# Power_stage.net
KiCad netlist of a schematic drawn in Altium Designer
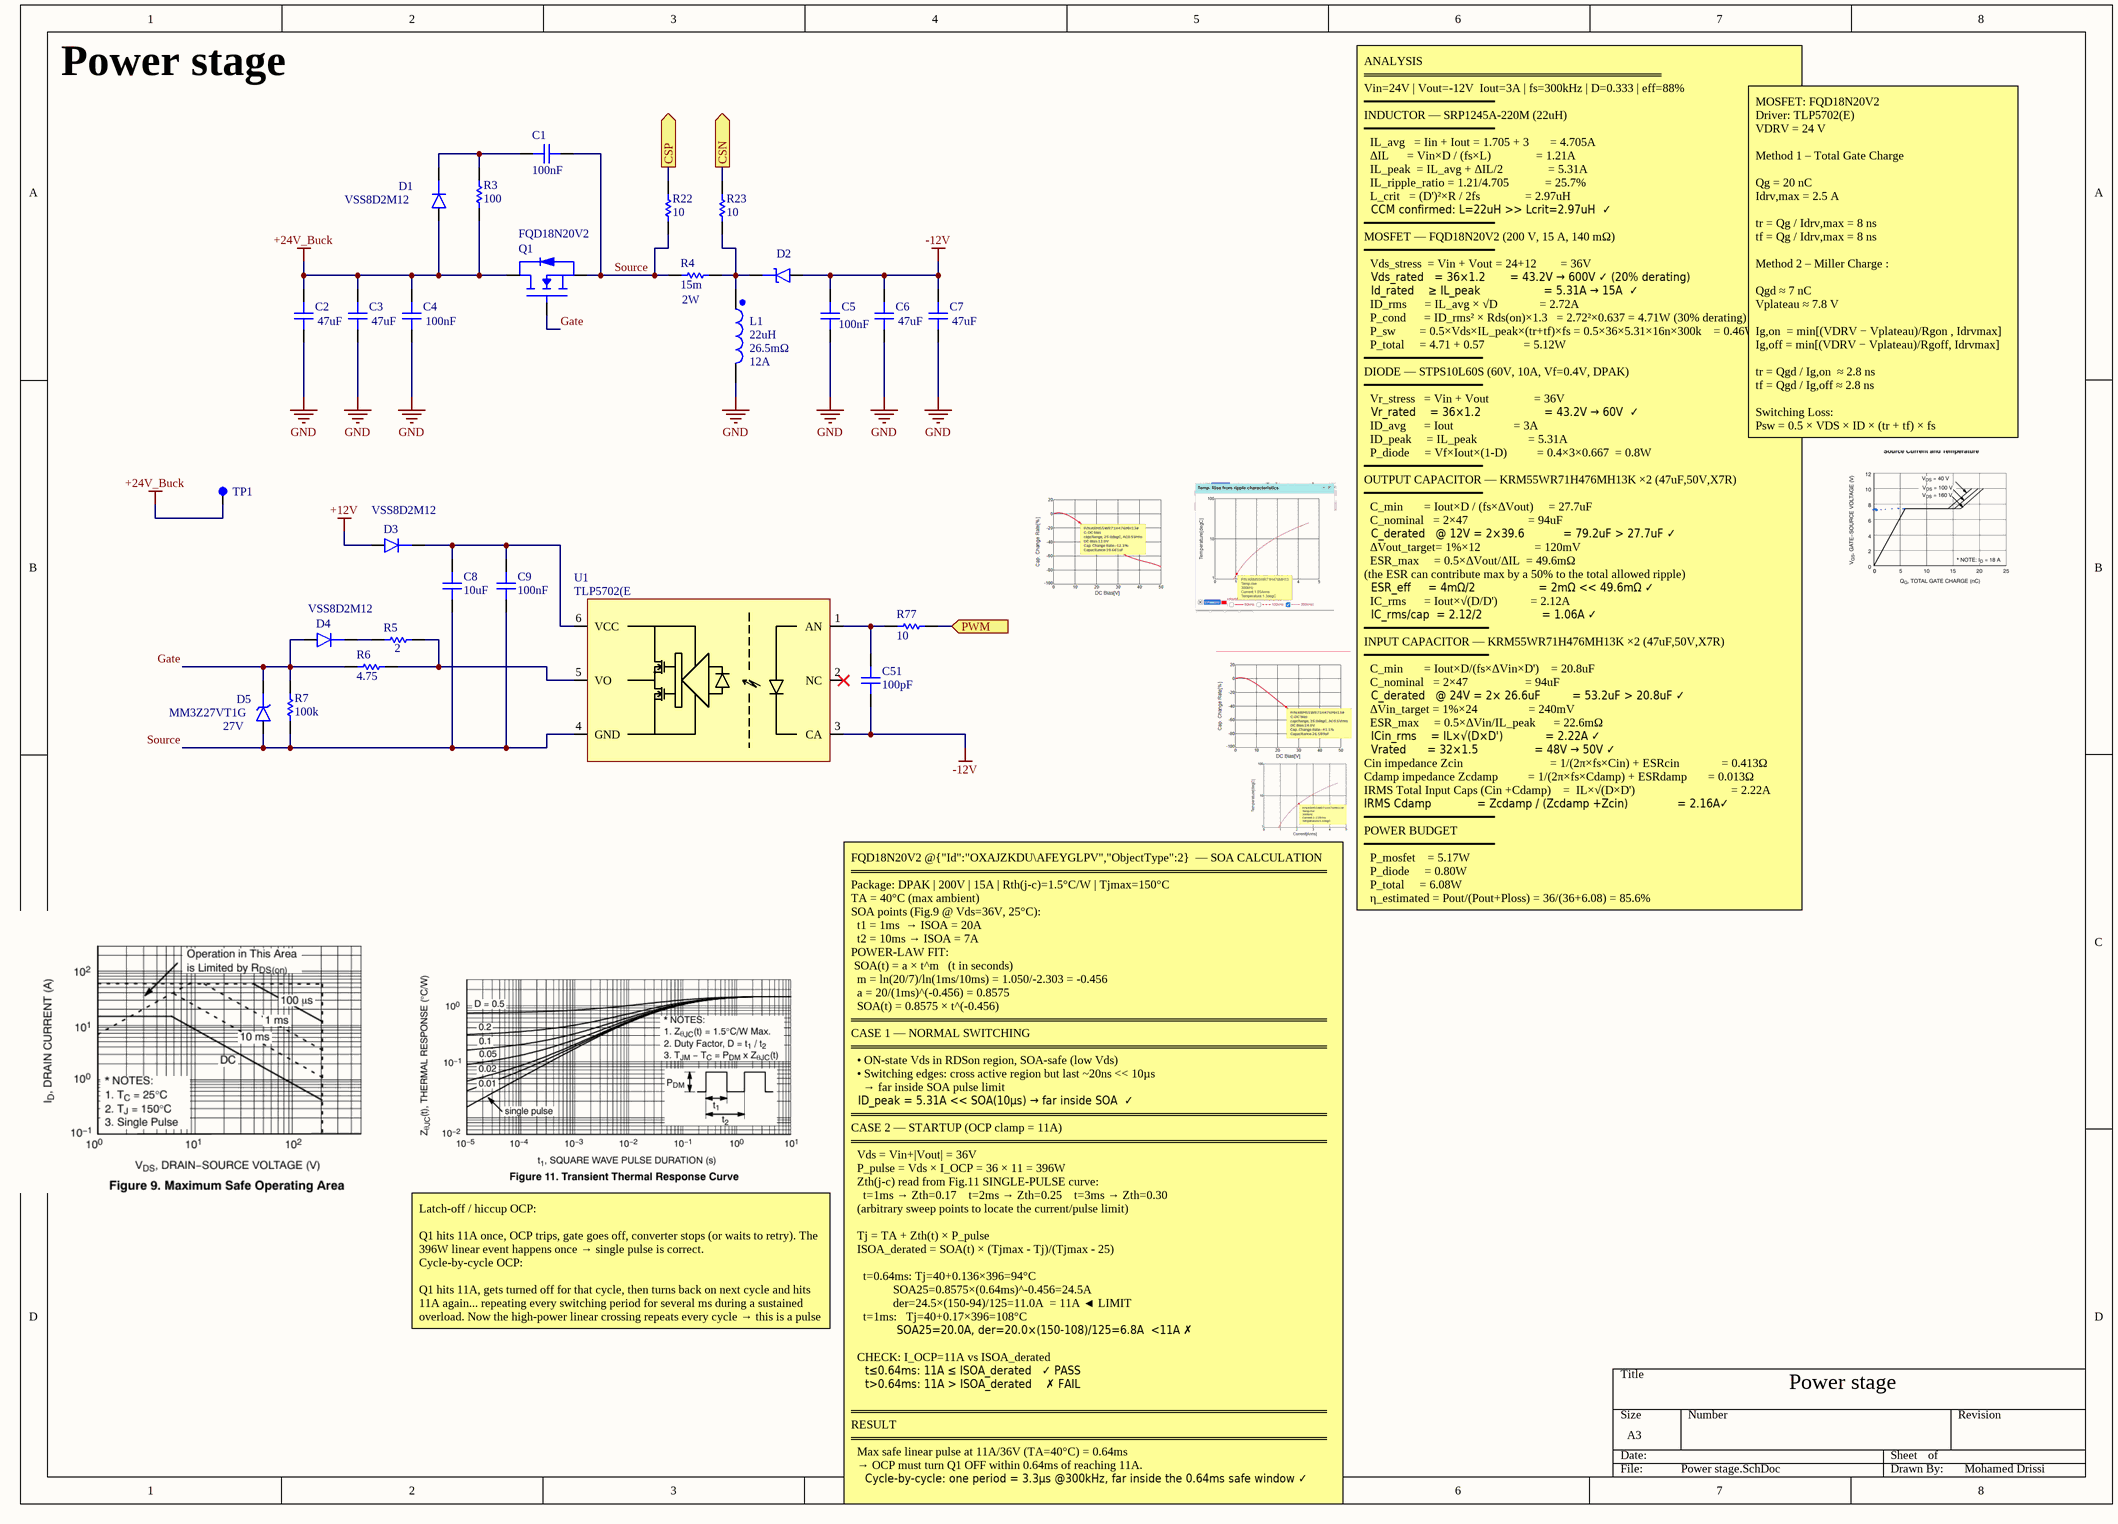
[diagram p0: Power stage.SchDoc]

(export (version "E")
  (design (tool "Eeschema 10.0.6"))
  (components
    (comp (ref "C1")
      (value "GMC10X7R104K100NT")
      (footprint "cap_0603")
      (description "100V 100nF X7R ±10% 0603 Multilayer Ceramic Capacitors MLCC - SMD/SMT ROHS")
      (fields (field (name "MANUFACTURER") "Cal-Chip Electronics") (field (name "CAPACITANCE") "100nF"))
      (libsource (lib "Inverting buck boost") (part "Cal-chip GMC10X7R104K100NT"))
    )
    (comp (ref "C2")
      (value "KRM55WR71H476MH13K")
      (footprint "cap_2220")
      (description "Multilayer Ceramic Capacitors MLCC - SMD/SMT 47uF 50VDC 20% X7R")
      (fields
        (field (name "MANUFACTURER") "Murata")
        (field (name "TOLERANCE") "20%")
        (field (name "CAPACITANCE") "47uF")
      )
      (libsource (lib "Inverting buck boost") (part "Murata KRM55WR71H476MH13K"))
    )
    (comp (ref "C3")
      (value "KRM55WR71H476MH13K")
      (footprint "cap_2220")
      (description "Multilayer Ceramic Capacitors MLCC - SMD/SMT 47uF 50VDC 20% X7R")
      (fields
        (field (name "MANUFACTURER") "Murata")
        (field (name "TOLERANCE") "20%")
        (field (name "CAPACITANCE") "47uF")
      )
      (libsource (lib "Inverting buck boost") (part "Murata KRM55WR71H476MH13K"))
    )
    (comp (ref "C4")
      (value "GMC10X7R104K100NT")
      (footprint "cap_0603")
      (description "100V 100nF X7R ±10% 0603 Multilayer Ceramic Capacitors MLCC - SMD/SMT ROHS")
      (fields (field (name "MANUFACTURER") "Cal-Chip Electronics") (field (name "CAPACITANCE") "100nF"))
      (libsource (lib "Inverting buck boost") (part "Cal-chip GMC10X7R104K100NT"))
    )
    (comp (ref "C5")
      (value "GMC10X7R104K100NT")
      (footprint "cap_0603")
      (description "100V 100nF X7R ±10% 0603 Multilayer Ceramic Capacitors MLCC - SMD/SMT ROHS")
      (fields (field (name "MANUFACTURER") "Cal-Chip Electronics") (field (name "CAPACITANCE") "100nF"))
      (libsource (lib "Inverting buck boost") (part "Cal-chip GMC10X7R104K100NT"))
    )
    (comp (ref "C6")
      (value "KRM55WR71H476MH13K")
      (footprint "cap_2220")
      (description "Multilayer Ceramic Capacitors MLCC - SMD/SMT 47uF 50VDC 20% X7R")
      (fields
        (field (name "MANUFACTURER") "Murata")
        (field (name "TOLERANCE") "20%")
        (field (name "CAPACITANCE") "47uF")
      )
      (libsource (lib "Inverting buck boost") (part "Murata KRM55WR71H476MH13K"))
    )
    (comp (ref "C7")
      (value "KRM55WR71H476MH13K")
      (footprint "cap_2220")
      (description "Multilayer Ceramic Capacitors MLCC - SMD/SMT 47uF 50VDC 20% X7R")
      (fields
        (field (name "MANUFACTURER") "Murata")
        (field (name "TOLERANCE") "20%")
        (field (name "CAPACITANCE") "47uF")
      )
      (libsource (lib "Inverting buck boost") (part "Murata KRM55WR71H476MH13K"))
    )
    (comp (ref "C8")
      (value "885012209073")
      (footprint "cap_1210")
      (description "Cap, 10Uf, 50V, Mlcc, 1210 Rohs Compliant: Yes ¦Würth Elektronik 885012209073")
      (fields
        (field (name "MANUFACTURER") "Wurth Elektronik")
        (field (name "TOLERANCE") "10%")
        (field (name "CAPACITANCE") "10uF")
      )
      (libsource (lib "Inverting buck boost") (part "Wurth 885012209073"))
    )
    (comp (ref "C9")
      (value "GMC10X7R104K100NT")
      (footprint "cap_0603")
      (description "100V 100nF X7R ±10% 0603 Multilayer Ceramic Capacitors MLCC - SMD/SMT ROHS")
      (fields (field (name "MANUFACTURER") "Cal-Chip Electronics") (field (name "CAPACITANCE") "100nF"))
      (libsource (lib "Inverting buck boost") (part "Cal-chip GMC10X7R104K100NT"))
    )
    (comp (ref "C51")
      (value "GCM1885C2A101JA16D")
      (footprint "Cap_0603")
      (description "100V 100pF C0G ±5% 0603 Multilayer Ceramic Capacitors MLCC - SMD/SMT ROHS")
      (fields
        (field (name "MANUFACTURER") "Murata")
        (field (name "TOLERANCE") "5%")
        (field (name "CAPACITANCE") "100pF")
      )
      (libsource (lib "Inverting buck boost") (part "Murata GCM1885C2A101JA16D"))
    )
    (comp (ref "D1")
      (value "VSS8D2M12")
      (footprint "DO-221AD")
      (description "Rectifier Diode, Schottky, 1 Phase, 1 Element, 2A, 120V V(RRM), Silicon, DO-221AD")
      (fields
        (field (name "MANUFACTURER") "Vishay")
        (field (name "MANUFACTURER PART NUMBER") "VSS8D2M12-M3/H")
      )
      (libsource (lib "Inverting buck boost") (part "Vishay VSS8D2M12-M3/H"))
    )
    (comp (ref "D2")
      (value "STPS10L60D")
      (footprint "TO-220")
      (description "Rectifier Diode, Schottky, 1 Phase, 1 Element, 10A, 60V V(RRM), Silicon, TO-220AC")
      (fields (field (name "MANUFACTURER") "STMicroelectronics"))
      (libsource (lib "Inverting buck boost") (part "ST STPS10L60D"))
    )
    (comp (ref "D3")
      (value "VSS8D2M12")
      (footprint "DO-221AD")
      (description "Rectifier Diode, Schottky, 1 Phase, 1 Element, 2A, 120V V(RRM), Silicon, DO-221AD")
      (fields
        (field (name "MANUFACTURER") "Vishay")
        (field (name "MANUFACTURER PART NUMBER") "VSS8D2M12-M3/H")
      )
      (libsource (lib "Inverting buck boost") (part "Vishay VSS8D2M12-M3/H"))
    )
    (comp (ref "D4")
      (value "VSS8D2M12")
      (footprint "DO-221AD")
      (description "Rectifier Diode, Schottky, 1 Phase, 1 Element, 2A, 120V V(RRM), Silicon, DO-221AD")
      (fields
        (field (name "MANUFACTURER") "Vishay")
        (field (name "MANUFACTURER PART NUMBER") "VSS8D2M12-M3/H")
      )
      (libsource (lib "Inverting buck boost") (part "Vishay VSS8D2M12-M3/H"))
    )
    (comp (ref "D5")
      (value "MM3Z27VT1G")
      (footprint "SOD-323")
      (description "Diode, Zener, Vr 27V, If 10MA, Pkg SOD-323, Vf 0.9V, Cj 70PF, Tj +150C, Pd 200MW, Ir 2MA")
      (fields
        (field (name "MANUFACTURER") "onsemi")
        (field (name "TOLERANCE") "7%")
        (field (name "REFERENCE VOLTAGE") "27V")
      )
      (libsource (lib "Inverting buck boost") (part "Onsemi MM3Z27VT1G"))
    )
    (comp (ref "L1")
      (value "MWLA1707S-220MT")
      (footprint "MWLA1707S")
      (description "General Purpose Inductor, 22uH, 20%, 1 Element, Wirewound-Core, SMD, 6967")
      (fields
        (field (name "MANUFACTURER") "Sunlord")
        (field (name "MAX CURRENT RATING") "12A")
        (field (name "TOLERANCE") "20%")
        (field (name "DC RESISTANCE (DCR)") "26.5mΩ")
        (field (name "INDUCTANCE") "22uH")
      )
      (libsource (lib "Inverting buck boost") (part "Shenzen MWLA1707S-220MT"))
    )
    (comp (ref "Q1")
      (value "FQD18N20V2")
      (footprint "TO-252  (DPAK)")
      (description "N-Channel Power MOSFET, QFET®, 200 V, 15 A, 140 mΩ, DPAK")
      (fields (field (name "MANUFACTURER") "onsemi") (field (name "MANUFACTURER PART NUMBER") "FQD18N20V2TM"))
      (libsource (lib "Inverting buck boost") (part "Onsemi FQD18N20V2TM"))
    )
    (comp (ref "R3")
      (value "CPA2512E1000FS-T10")
      (footprint "res_2512")
      (fields
        (field (name "MANUFACTURER") "Susumu")
        (field (name "TOLERANCE") "1%")
        (field (name "RESISTANCE") "100")
      )
      (libsource (lib "Inverting buck boost") (part "Susumu CPA2512E1000FS-T10"))
    )
    (comp (ref "R4")
      (value "D1MPAB2512QR015FA-T4")
      (footprint "res_2512")
      (description "Res 0.015 Ohm 1% 2W 2512")
      (fields
        (field (name "MANUFACTURER") "Thin Film Tech")
        (field (name "RESISTANCE") "15m")
        (field (name "POWER") "2W")
      )
      (libsource (lib "Inverting buck boost") (part "Thin Film D1MPAB2512QR015FA-T4"))
    )
    (comp (ref "R5")
      (value "2")
      (footprint "res_0603")
      (description "Res Thick Film 0603 2 Ohm 1% 0.1W(1/10W) ±100ppm/C Pad SMD T/R Automotive AEC-Q200")
      (fields
        (field (name "MANUFACTURER") "Vishay")
        (field (name "MANUFACTURER PART NUMBER") "CRCW06032R00FKEA")
      )
      (libsource (lib "Inverting buck boost") (part "Vishay CRCW06032R00FKEA"))
    )
    (comp (ref "R6")
      (value "4.75")
      (footprint "res_0603")
      (fields
        (field (name "MANUFACTURER") "Vishay")
        (field (name "MANUFACTURER PART NUMBER") "CRCW06034R75FKEAHP")
        (field (name "TOLERANCE") "1%")
      )
      (libsource (lib "Inverting buck boost") (part "Vishay CRCW06034R75FKEAHP"))
    )
    (comp (ref "R7")
      (value "CRCW0603100KFKEA")
      (footprint "res_0603")
      (description "Res Thick Film 0603 100K Ohm 1% 1/3W ±100ppm/°C Molded SMD SMD Paper T/R")
      (fields
        (field (name "MANUFACTURER") "Vishay")
        (field (name "MANUFACTURER PART NUMBER") "CRCW0603100KFKEAHP")
        (field (name "RESISTANCE") "100k")
      )
      (libsource (lib "Inverting buck boost") (part "Vishay CRCW0603100KFKEAHP"))
    )
    (comp (ref "R22")
      (value "RC0603FR-0710RL")
      (footprint "res_0603")
      (description "Res Thick Film 0603 1K Ohm 1% 0.1W(1/10W) ±100ppm/°C Pad SMD T/R / RES SMD 1K OHM 1% 1/10W 0603")
      (fields
        (field (name "RESISTANCE") "10")
        (field (name "MANUFACTURER") "Yageo Group")
        (field (name "MANUFACTURER PART NUMBER") "RC0603FR-071KL")
      )
      (libsource (lib "Inverting buck boost") (part "Yageo RC0603FR-0710RL"))
    )
    (comp (ref "R23")
      (value "RC0603FR-0710RL")
      (footprint "res_0603")
      (description "Res Thick Film 0603 1K Ohm 1% 0.1W(1/10W) ±100ppm/°C Pad SMD T/R / RES SMD 1K OHM 1% 1/10W 0603")
      (fields
        (field (name "RESISTANCE") "10")
        (field (name "MANUFACTURER") "Yageo Group")
        (field (name "MANUFACTURER PART NUMBER") "RC0603FR-071KL")
      )
      (libsource (lib "Inverting buck boost") (part "Yageo RC0603FR-0710RL"))
    )
    (comp (ref "R77")
      (value "RT0603BRE0710RL")
      (footprint "res_0603")
      (description "Fixed Resistor, Thin Film, 0.1W, 10ohm, 75V, 0.1% +/-Tol, 50ppm/Cel, Surface Mount, 0603")
      (fields
        (field (name "MANUFACTURER") "Yageo Group")
        (field (name "TOLERANCE") "0.1%")
        (field (name "RESISITANCE") "10")
      )
      (libsource (lib "Inverting buck boost") (part "Yageo RT0603BRE0710RL"))
    )
    (comp (ref "TP1")
      (value "5000")
      (footprint "TH TP")
      (description "Cable Wrap, 1/2 Inch, Polyethylene, Natural, 50 Ft, Spirap Series ¦ TE Connectivity 500002-1")
      (fields (field (name "MANUFACTURER") "Keystone"))
      (libsource (lib "Inverting buck boost") (part "Keystone 5000"))
    )
    (comp (ref "U1")
      (value "TLP5702(E")
      (footprint "TOSHIBA: 11-4N1A")
      (description "Optocoupler DC-IN Single Totem-Pole-OUT 6-Pin SOIC Magazine")
      (fields (field (name "MANUFACTURER") "Toshiba"))
      (libsource (lib "Inverting buck boost") (part "Toshiba TLP5702(E"))
    )
  )
  (nets
    (net (code "1") (name "+12V") (class "Default")
      (node (ref "D3") (pin "A") (pinfunction "A_A") (pintype "passive"))
    )
    (net (code "2") (name "+24V_Buck") (class "Default")
      (node (ref "C2") (pin "2") (pinfunction "2_2") (pintype "passive"))
      (node (ref "C3") (pin "2") (pinfunction "2_2") (pintype "passive"))
      (node (ref "C4") (pin "2") (pinfunction "2_2") (pintype "passive"))
      (node (ref "D1") (pin "A") (pinfunction "A_A") (pintype "passive"))
      (node (ref "Q1") (pin "2") (pinfunction "D_2") (pintype "passive"))
      (node (ref "R3") (pin "1") (pinfunction "1_1") (pintype "passive"))
      (node (ref "TP1") (pin "1") (pinfunction "1_1") (pintype "passive"))
    )
    (net (code "3") (name "-12V") (class "Default")
      (node (ref "C5") (pin "2") (pinfunction "2_2") (pintype "passive"))
      (node (ref "C51") (pin "1") (pinfunction "1_1") (pintype "passive"))
      (node (ref "C6") (pin "2") (pinfunction "2_2") (pintype "passive"))
      (node (ref "C7") (pin "2") (pinfunction "2_2") (pintype "passive"))
      (node (ref "D2") (pin "2") (pinfunction "A_2") (pintype "passive"))
      (node (ref "U1") (pin "3") (pinfunction "CA_3") (pintype "passive"))
    )
    (net (code "4") (name "/CSN") (class "Default")
      (node (ref "R23") (pin "2") (pinfunction "2_2") (pintype "passive"))
    )
    (net (code "5") (name "/CSP") (class "Default")
      (node (ref "R22") (pin "2") (pinfunction "2_2") (pintype "passive"))
    )
    (net (code "6") (name "/Gate") (class "Default")
      (node (ref "D4") (pin "A") (pinfunction "A_A") (pintype "passive"))
      (node (ref "D5") (pin "k") (pinfunction "C_k") (pintype "passive"))
      (node (ref "Q1") (pin "1") (pinfunction "G_1") (pintype "passive"))
      (node (ref "R6") (pin "1") (pinfunction "1_1") (pintype "passive"))
      (node (ref "R7") (pin "2") (pinfunction "2_2") (pintype "passive"))
    )
    (net (code "7") (name "/PWM") (class "Default")
      (node (ref "R77") (pin "2") (pinfunction "2_2") (pintype "passive"))
    )
    (net (code "8") (name "/Source") (class "Default")
      (node (ref "C1") (pin "1") (pinfunction "1_1") (pintype "passive"))
      (node (ref "C8") (pin "1") (pinfunction "1_1") (pintype "passive"))
      (node (ref "C9") (pin "1") (pinfunction "1_1") (pintype "passive"))
      (node (ref "D5") (pin "A") (pinfunction "A_A") (pintype "passive"))
      (node (ref "Q1") (pin "3") (pinfunction "S_3") (pintype "passive"))
      (node (ref "R22") (pin "1") (pinfunction "1_1") (pintype "passive"))
      (node (ref "R4") (pin "1") (pinfunction "1_1") (pintype "passive"))
      (node (ref "R7") (pin "1") (pinfunction "1_1") (pintype "passive"))
      (node (ref "U1") (pin "4") (pinfunction "GND_4") (pintype "passive"))
    )
    (net (code "9") (name "GND") (class "Default")
      (node (ref "C2") (pin "1") (pinfunction "1_1") (pintype "passive"))
      (node (ref "C3") (pin "1") (pinfunction "1_1") (pintype "passive"))
      (node (ref "C4") (pin "1") (pinfunction "1_1") (pintype "passive"))
      (node (ref "C5") (pin "1") (pinfunction "1_1") (pintype "passive"))
      (node (ref "C6") (pin "1") (pinfunction "1_1") (pintype "passive"))
      (node (ref "C7") (pin "1") (pinfunction "1_1") (pintype "passive"))
      (node (ref "L1") (pin "2") (pinfunction "2_2") (pintype "passive"))
    )
    (net (code "10") (name "Net-(C1-Pad2)") (class "Default")
      (node (ref "C1") (pin "2") (pinfunction "2_2") (pintype "passive"))
      (node (ref "D1") (pin "C") (pinfunction "C_C") (pintype "passive"))
      (node (ref "R3") (pin "2") (pinfunction "2_2") (pintype "passive"))
    )
    (net (code "11") (name "Net-(D2-K)") (class "Default")
      (node (ref "D2") (pin "1") (pinfunction "K_1") (pintype "passive"))
      (node (ref "L1") (pin "1") (pinfunction "1_1") (pintype "passive"))
      (node (ref "R23") (pin "1") (pinfunction "1_1") (pintype "passive"))
      (node (ref "R4") (pin "2") (pinfunction "2_2") (pintype "passive"))
    )
    (net (code "12") (name "Net-(D4-PadC)") (class "Default")
      (node (ref "D4") (pin "C") (pinfunction "C_C") (pintype "passive"))
      (node (ref "R5") (pin "1") (pinfunction "1_1") (pintype "passive"))
    )
    (net (code "13") (name "Net-(U1-AN)") (class "Default")
      (node (ref "C51") (pin "2") (pinfunction "2_2") (pintype "passive"))
      (node (ref "R77") (pin "1") (pinfunction "1_1") (pintype "passive"))
      (node (ref "U1") (pin "1") (pinfunction "AN_1") (pintype "passive"))
    )
    (net (code "14") (name "Net-(U1-VCC)") (class "Default")
      (node (ref "C8") (pin "2") (pinfunction "2_2") (pintype "passive"))
      (node (ref "C9") (pin "2") (pinfunction "2_2") (pintype "passive"))
      (node (ref "D3") (pin "C") (pinfunction "C_C") (pintype "passive"))
      (node (ref "U1") (pin "6") (pinfunction "VCC_6") (pintype "power_in"))
    )
    (net (code "15") (name "Net-(U1-VO)") (class "Default")
      (node (ref "R5") (pin "2") (pinfunction "2_2") (pintype "passive"))
      (node (ref "R6") (pin "2") (pinfunction "2_2") (pintype "passive"))
      (node (ref "U1") (pin "5") (pinfunction "VO_5") (pintype "open_collector"))
    )
    (net (code "16") (name "unconnected-(U1-NC-Pad2)") (class "Default")
      (node (ref "U1") (pin "2") (pinfunction "NC_2") (pintype "passive+no_connect"))
    )
  )
)
